# ISOLATION.net
KiCad netlist of a schematic drawn in Altium Designer
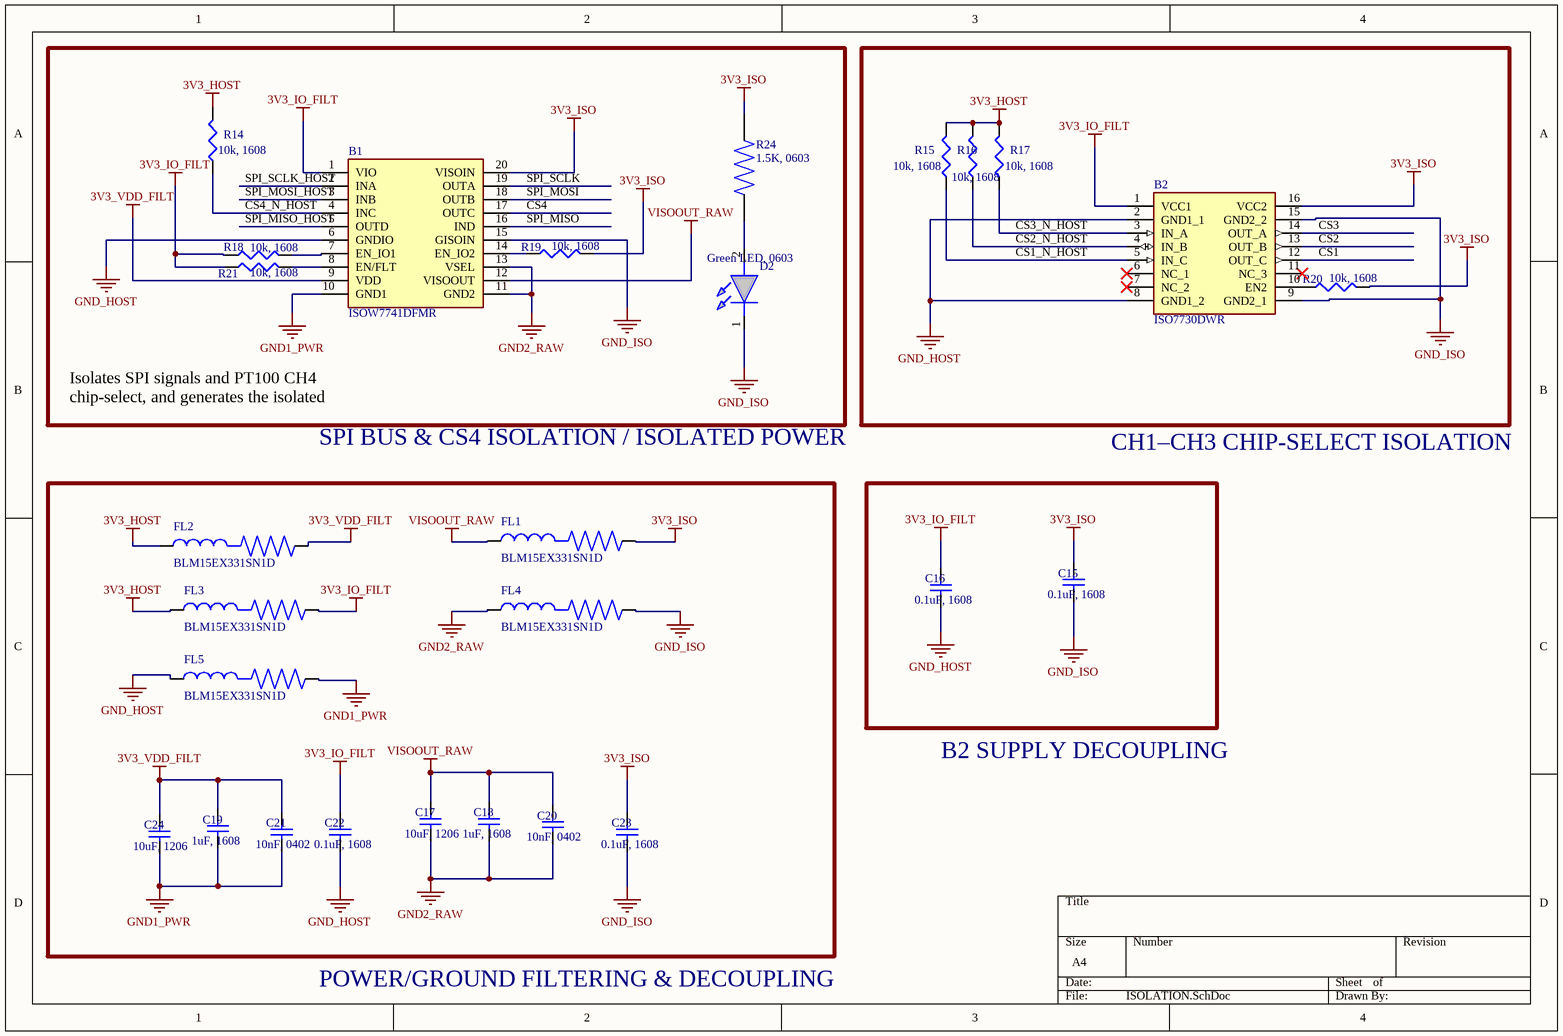
[diagram p0: ISOLATION.SchDoc]

(export (version "E")
  (design (tool "Eeschema 10.0.6"))
  (components
    (comp (ref "B1")
      (value "ISOW7741DFMR")
      (footprint "SOIC127P1030X355-20N")
      (description "ISOW7741 Quad-Channel Digital Isolator with Integrated Low-Emissions, Low-Noise DC-DC Converter")
      (fields (field (name "MOUSER PART NUMBER") "595-ISOW7741DFMR"))
      (libsource (lib "ISOW7741DFMR") (part "ISOW7741DFMR"))
    )
    (comp (ref "B2")
      (value "ISO7730DWR")
      (footprint "SamacSys:SOIC127P1030X265-16N")
      (description "Integrated Circuit")
      (fields (field (name "MOUSER PART NUMBER") "595-ISO7730DWR"))
      (libsource (lib "SamacSys") (part "ISO7730DWR"))
    )
    (comp (ref "C15")
      (value "0.1uF, 1608")
      (footprint "1608[0603]")
      (description "Capacitor (Semiconductor SIM Model)")
      (fields (field (name "PUBLISHER") "Altium Limited"))
      (libsource (lib "Miscellaneous Devices") (part "Cap Semi"))
    )
    (comp (ref "C16")
      (value "0.1uF, 1608")
      (footprint "1608[0603]")
      (description "Capacitor (Semiconductor SIM Model)")
      (fields (field (name "PUBLISHER") "Altium Limited"))
      (libsource (lib "Miscellaneous Devices") (part "Cap Semi"))
    )
    (comp (ref "C17")
      (value "10uF, 1206")
      (footprint "C1206")
      (description "C1206C106J3RACTU")
      (fields (field (name "PUBLISHER") "Altium Limited"))
      (libsource (lib "Miscellaneous Devices") (part "Cap Semi"))
    )
    (comp (ref "C18")
      (value "1uF, 1608")
      (footprint "1608[0603]")
      (description "Capacitor (Semiconductor SIM Model)")
      (fields (field (name "PUBLISHER") "Altium Limited"))
      (libsource (lib "Miscellaneous Devices") (part "Cap Semi"))
    )
    (comp (ref "C19")
      (value "1uF, 1608")
      (footprint "1608[0603]")
      (description "Capacitor (Semiconductor SIM Model)")
      (fields (field (name "PUBLISHER") "Altium Limited"))
      (libsource (lib "Miscellaneous Devices") (part "Cap Semi"))
    )
    (comp (ref "C20")
      (value "10nF, 0402")
      (footprint "0402")
      (description "Capacitor (Semiconductor SIM Model)")
      (fields (field (name "PUBLISHER") "Altium Limited"))
      (libsource (lib "Miscellaneous Devices") (part "Cap Semi"))
    )
    (comp (ref "C21")
      (value "10nF, 0402")
      (footprint "0402")
      (description "Capacitor (Semiconductor SIM Model)")
      (fields (field (name "PUBLISHER") "Altium Limited"))
      (libsource (lib "Miscellaneous Devices") (part "Cap Semi"))
    )
    (comp (ref "C22")
      (value "0.1uF, 1608")
      (footprint "1608[0603]")
      (description "Capacitor (Semiconductor SIM Model)")
      (fields (field (name "PUBLISHER") "Altium Limited"))
      (libsource (lib "Miscellaneous Devices") (part "Cap Semi"))
    )
    (comp (ref "C23")
      (value "0.1uF, 1608")
      (footprint "1608[0603]")
      (description "Capacitor (Semiconductor SIM Model)")
      (fields (field (name "PUBLISHER") "Altium Limited"))
      (libsource (lib "Miscellaneous Devices") (part "Cap Semi"))
    )
    (comp (ref "C24")
      (value "10uF, 1206")
      (footprint "C1206")
      (description "C1206C106J3RACTU")
      (fields (field (name "PUBLISHER") "Altium Limited"))
      (libsource (lib "Miscellaneous Devices") (part "Cap Semi"))
    )
    (comp (ref "D2")
      (value "Green LED, 0603")
      (footprint "LEDC1608X75N")
      (fields (field (name "MANUFACTURER_PART_NUMBER") "KPH-1608SGC"))
      (libsource (lib "KPH-1608SGC") (part "KPH-1608SGC"))
    )
    (comp (ref "FL1")
      (value "BLM15EX331SN1D")
      (footprint "BEADC1005X55N")
      (description "330 Ohms @ 100 MHz 1 Power, Signal Line Ferrite Bead 0402 (1005 Metric) 1.1A 205mOhm")
      (fields (field (name "MF") "Murata"))
      (libsource (lib "BLM15EX331SN1D") (part "BLM15EX331SN1D"))
    )
    (comp (ref "FL2")
      (value "BLM15EX331SN1D")
      (footprint "BEADC1005X55N")
      (description "330 Ohms @ 100 MHz 1 Power, Signal Line Ferrite Bead 0402 (1005 Metric) 1.1A 205mOhm")
      (fields (field (name "MF") "Murata"))
      (libsource (lib "BLM15EX331SN1D") (part "BLM15EX331SN1D"))
    )
    (comp (ref "FL3")
      (value "BLM15EX331SN1D")
      (footprint "BEADC1005X55N")
      (description "330 Ohms @ 100 MHz 1 Power, Signal Line Ferrite Bead 0402 (1005 Metric) 1.1A 205mOhm")
      (fields (field (name "MF") "Murata"))
      (libsource (lib "BLM15EX331SN1D") (part "BLM15EX331SN1D"))
    )
    (comp (ref "FL4")
      (value "BLM15EX331SN1D")
      (footprint "BEADC1005X55N")
      (description "330 Ohms @ 100 MHz 1 Power, Signal Line Ferrite Bead 0402 (1005 Metric) 1.1A 205mOhm")
      (fields (field (name "MF") "Murata"))
      (libsource (lib "BLM15EX331SN1D") (part "BLM15EX331SN1D"))
    )
    (comp (ref "FL5")
      (value "BLM15EX331SN1D")
      (footprint "BEADC1005X55N")
      (description "330 Ohms @ 100 MHz 1 Power, Signal Line Ferrite Bead 0402 (1005 Metric) 1.1A 205mOhm")
      (fields (field (name "MF") "Murata"))
      (libsource (lib "BLM15EX331SN1D") (part "BLM15EX331SN1D"))
    )
    (comp (ref "R14")
      (value "10k, 1608")
      (footprint "J1-0603")
      (description "Resistor")
      (fields (field (name "PUBLISHER") "Altium Limited"))
      (libsource (lib "Miscellaneous Devices") (part "Res3"))
    )
    (comp (ref "R15")
      (value "10k, 1608")
      (footprint "J1-0603")
      (description "Resistor")
      (fields (field (name "PUBLISHER") "Altium Limited"))
      (libsource (lib "Miscellaneous Devices") (part "Res3"))
    )
    (comp (ref "R16")
      (value "10k, 1608")
      (footprint "J1-0603")
      (description "Resistor")
      (fields (field (name "PUBLISHER") "Altium Limited"))
      (libsource (lib "Miscellaneous Devices") (part "Res3"))
    )
    (comp (ref "R17")
      (value "10k, 1608")
      (footprint "J1-0603")
      (description "Resistor")
      (fields (field (name "PUBLISHER") "Altium Limited"))
      (libsource (lib "Miscellaneous Devices") (part "Res3"))
    )
    (comp (ref "R18")
      (value "10k, 1608")
      (footprint "J1-0603")
      (description "Resistor")
      (fields (field (name "PUBLISHER") "Altium Limited"))
      (libsource (lib "Miscellaneous Devices") (part "Res3"))
    )
    (comp (ref "R19")
      (value "10k, 1608")
      (footprint "J1-0603")
      (description "Resistor")
      (fields (field (name "PUBLISHER") "Altium Limited"))
      (libsource (lib "Miscellaneous Devices") (part "Res3"))
    )
    (comp (ref "R20")
      (value "10k, 1608")
      (footprint "J1-0603")
      (description "Resistor")
      (fields (field (name "PUBLISHER") "Altium Limited"))
      (libsource (lib "Miscellaneous Devices") (part "Res3"))
    )
    (comp (ref "R21")
      (value "10k, 1608")
      (footprint "J1-0603")
      (description "Resistor")
      (fields (field (name "PUBLISHER") "Altium Limited"))
      (libsource (lib "Miscellaneous Devices") (part "Res3"))
    )
    (comp (ref "R24")
      (value "1.5K, 0603")
      (footprint "RESC1607X60N")
      (description "1.5 kOhms Â±1% 0.1W, 1/10W Chip Resistor 0603 (1608 Metric) Moisture Resistant Thick Film")
      (fields (field (name "MF") "Yageo") (field (name "MP") "RC0603FR-071K5L"))
      (libsource (lib "RC0603FR-071K5L") (part "RC0603FR-071K5L"))
    )
  )
  (nets
    (net (code "1") (name "/CS1") (class "Default")
      (node (ref "B2") (pin "12") (pinfunction "OUT_C_12") (pintype "output"))
    )
    (net (code "2") (name "/CS1_N_HOST") (class "Default")
      (node (ref "B2") (pin "5") (pinfunction "IN_C_5") (pintype "input"))
      (node (ref "R15") (pin "1") (pinfunction "1_1") (pintype "passive"))
    )
    (net (code "3") (name "/CS2") (class "Default")
      (node (ref "B2") (pin "13") (pinfunction "OUT_B_13") (pintype "output"))
    )
    (net (code "4") (name "/CS2_N_HOST") (class "Default")
      (node (ref "B2") (pin "4") (pinfunction "IN_B_4") (pintype "bidirectional"))
      (node (ref "R16") (pin "1") (pinfunction "1_1") (pintype "passive"))
    )
    (net (code "5") (name "/CS3") (class "Default")
      (node (ref "B2") (pin "14") (pinfunction "OUT_A_14") (pintype "output"))
    )
    (net (code "6") (name "/CS3_N_HOST") (class "Default")
      (node (ref "B2") (pin "3") (pinfunction "IN_A_3") (pintype "input"))
      (node (ref "R17") (pin "1") (pinfunction "1_1") (pintype "passive"))
    )
    (net (code "7") (name "/CS4") (class "Default")
      (node (ref "B1") (pin "17") (pinfunction "OUTC_17") (pintype "passive"))
    )
    (net (code "8") (name "/CS4_N_HOST") (class "Default")
      (node (ref "B1") (pin "4") (pinfunction "INC_4") (pintype "passive"))
      (node (ref "R14") (pin "1") (pinfunction "1_1") (pintype "passive"))
    )
    (net (code "9") (name "/SPI_MISO") (class "Default")
      (node (ref "B1") (pin "16") (pinfunction "IND_16") (pintype "passive"))
    )
    (net (code "10") (name "/SPI_MISO_HOST") (class "Default")
      (node (ref "B1") (pin "5") (pinfunction "OUTD_5") (pintype "passive"))
    )
    (net (code "11") (name "/SPI_MOSI") (class "Default")
      (node (ref "B1") (pin "18") (pinfunction "OUTB_18") (pintype "passive"))
    )
    (net (code "12") (name "/SPI_MOSI_HOST") (class "Default")
      (node (ref "B1") (pin "3") (pinfunction "INB_3") (pintype "passive"))
    )
    (net (code "13") (name "/SPI_SCLK") (class "Default")
      (node (ref "B1") (pin "19") (pinfunction "OUTA_19") (pintype "passive"))
    )
    (net (code "14") (name "/SPI_SCLK_HOST") (class "Default")
      (node (ref "B1") (pin "2") (pinfunction "INA_2") (pintype "passive"))
    )
    (net (code "15") (name "3V3_HOST") (class "Default")
      (node (ref "FL2") (pin "1") (pinfunction "1_1") (pintype "passive"))
      (node (ref "FL3") (pin "1") (pinfunction "1_1") (pintype "passive"))
      (node (ref "R14") (pin "2") (pinfunction "2_2") (pintype "passive"))
      (node (ref "R15") (pin "2") (pinfunction "2_2") (pintype "passive"))
      (node (ref "R16") (pin "2") (pinfunction "2_2") (pintype "passive"))
      (node (ref "R17") (pin "2") (pinfunction "2_2") (pintype "passive"))
    )
    (net (code "16") (name "3V3_IO_FILT") (class "Default")
      (node (ref "B1") (pin "1") (pinfunction "VIO_1") (pintype "passive"))
      (node (ref "B2") (pin "1") (pinfunction "VCC1_1") (pintype "power_in"))
      (node (ref "C16") (pin "2") (pinfunction "2_2") (pintype "passive"))
      (node (ref "C22") (pin "2") (pinfunction "2_2") (pintype "passive"))
      (node (ref "FL3") (pin "2") (pinfunction "2_2") (pintype "passive"))
      (node (ref "R18") (pin "1") (pinfunction "1_1") (pintype "passive"))
      (node (ref "R21") (pin "1") (pinfunction "1_1") (pintype "passive"))
    )
    (net (code "17") (name "3V3_ISO") (class "Default")
      (node (ref "B1") (pin "20") (pinfunction "VISOIN_20") (pintype "passive"))
      (node (ref "B2") (pin "16") (pinfunction "VCC2_16") (pintype "power_in"))
      (node (ref "C15") (pin "2") (pinfunction "2_2") (pintype "passive"))
      (node (ref "C23") (pin "2") (pinfunction "2_2") (pintype "passive"))
      (node (ref "FL1") (pin "2") (pinfunction "2_2") (pintype "passive"))
      (node (ref "R19") (pin "2") (pinfunction "2_2") (pintype "passive"))
      (node (ref "R20") (pin "2") (pinfunction "2_2") (pintype "passive"))
      (node (ref "R24") (pin "1") (pinfunction "1_1") (pintype "passive"))
    )
    (net (code "18") (name "3V3_VDD_FILT") (class "Default")
      (node (ref "B1") (pin "9") (pinfunction "VDD_9") (pintype "passive"))
      (node (ref "C19") (pin "2") (pinfunction "2_2") (pintype "passive"))
      (node (ref "C21") (pin "2") (pinfunction "2_2") (pintype "passive"))
      (node (ref "C24") (pin "2") (pinfunction "2_2") (pintype "passive"))
      (node (ref "FL2") (pin "2") (pinfunction "2_2") (pintype "passive"))
    )
    (net (code "19") (name "GND1_PWR") (class "Default")
      (node (ref "B1") (pin "10") (pinfunction "GND1_10") (pintype "passive"))
      (node (ref "C19") (pin "1") (pinfunction "1_1") (pintype "passive"))
      (node (ref "C21") (pin "1") (pinfunction "1_1") (pintype "passive"))
      (node (ref "C24") (pin "1") (pinfunction "1_1") (pintype "passive"))
      (node (ref "FL5") (pin "2") (pinfunction "2_2") (pintype "passive"))
    )
    (net (code "20") (name "GND2_RAW") (class "Default")
      (node (ref "B1") (pin "11") (pinfunction "GND2_11") (pintype "passive"))
      (node (ref "B1") (pin "13") (pinfunction "VSEL_13") (pintype "passive"))
      (node (ref "C17") (pin "1") (pinfunction "1_1") (pintype "passive"))
      (node (ref "C18") (pin "1") (pinfunction "1_1") (pintype "passive"))
      (node (ref "C20") (pin "1") (pinfunction "1_1") (pintype "passive"))
      (node (ref "FL4") (pin "1") (pinfunction "1_1") (pintype "passive"))
    )
    (net (code "21") (name "GND_HOST") (class "Default")
      (node (ref "B1") (pin "6") (pinfunction "GNDIO_6") (pintype "passive"))
      (node (ref "B2") (pin "2") (pinfunction "GND1_1_2") (pintype "power_in"))
      (node (ref "B2") (pin "8") (pinfunction "GND1_2_8") (pintype "power_in"))
      (node (ref "C16") (pin "1") (pinfunction "1_1") (pintype "passive"))
      (node (ref "C22") (pin "1") (pinfunction "1_1") (pintype "passive"))
      (node (ref "FL5") (pin "1") (pinfunction "1_1") (pintype "passive"))
    )
    (net (code "22") (name "GND_ISO") (class "Default")
      (node (ref "B1") (pin "15") (pinfunction "GISOIN_15") (pintype "passive"))
      (node (ref "B2") (pin "15") (pinfunction "GND2_2_15") (pintype "power_in"))
      (node (ref "B2") (pin "9") (pinfunction "GND2_1_9") (pintype "power_in"))
      (node (ref "C15") (pin "1") (pinfunction "1_1") (pintype "passive"))
      (node (ref "C23") (pin "1") (pinfunction "1_1") (pintype "passive"))
      (node (ref "D2") (pin "1") (pinfunction "K_1") (pintype "passive"))
      (node (ref "FL4") (pin "2") (pinfunction "2_2") (pintype "passive"))
    )
    (net (code "23") (name "Net-(B1-EN_IO1)") (class "Default")
      (node (ref "B1") (pin "7") (pinfunction "EN_IO1_7") (pintype "passive"))
      (node (ref "R18") (pin "2") (pinfunction "2_2") (pintype "passive"))
    )
    (net (code "24") (name "Net-(B1-EN_IO2)") (class "Default")
      (node (ref "B1") (pin "14") (pinfunction "EN_IO2_14") (pintype "passive"))
      (node (ref "R19") (pin "1") (pinfunction "1_1") (pintype "passive"))
    )
    (net (code "25") (name "Net-(B1-EN{slash}FLT)") (class "Default")
      (node (ref "B1") (pin "8") (pinfunction "EN/FLT_8") (pintype "passive"))
      (node (ref "R21") (pin "2") (pinfunction "2_2") (pintype "passive"))
    )
    (net (code "26") (name "Net-(B2-EN2)") (class "Default")
      (node (ref "B2") (pin "10") (pinfunction "EN2_10") (pintype "passive"))
      (node (ref "R20") (pin "1") (pinfunction "1_1") (pintype "passive"))
    )
    (net (code "27") (name "Net-(D2-A)") (class "Default")
      (node (ref "D2") (pin "2") (pinfunction "A_2") (pintype "passive"))
      (node (ref "R24") (pin "2") (pinfunction "2_2") (pintype "passive"))
    )
    (net (code "28") (name "VISOOUT_RAW") (class "Default")
      (node (ref "B1") (pin "12") (pinfunction "VISOOUT_12") (pintype "passive"))
      (node (ref "C17") (pin "2") (pinfunction "2_2") (pintype "passive"))
      (node (ref "C18") (pin "2") (pinfunction "2_2") (pintype "passive"))
      (node (ref "C20") (pin "2") (pinfunction "2_2") (pintype "passive"))
      (node (ref "FL1") (pin "1") (pinfunction "1_1") (pintype "passive"))
    )
    (net (code "29") (name "unconnected-(B2-NC_1-Pad6)") (class "Default")
      (node (ref "B2") (pin "6") (pinfunction "NC_1_6") (pintype "passive+no_connect"))
    )
    (net (code "30") (name "unconnected-(B2-NC_2-Pad7)") (class "Default")
      (node (ref "B2") (pin "7") (pinfunction "NC_2_7") (pintype "passive+no_connect"))
    )
    (net (code "31") (name "unconnected-(B2-NC_3-Pad11)") (class "Default")
      (node (ref "B2") (pin "11") (pinfunction "NC_3_11") (pintype "passive+no_connect"))
    )
  )
)
